# LatchDelay.net
KiCad netlist of a schematic drawn in Altium Designer
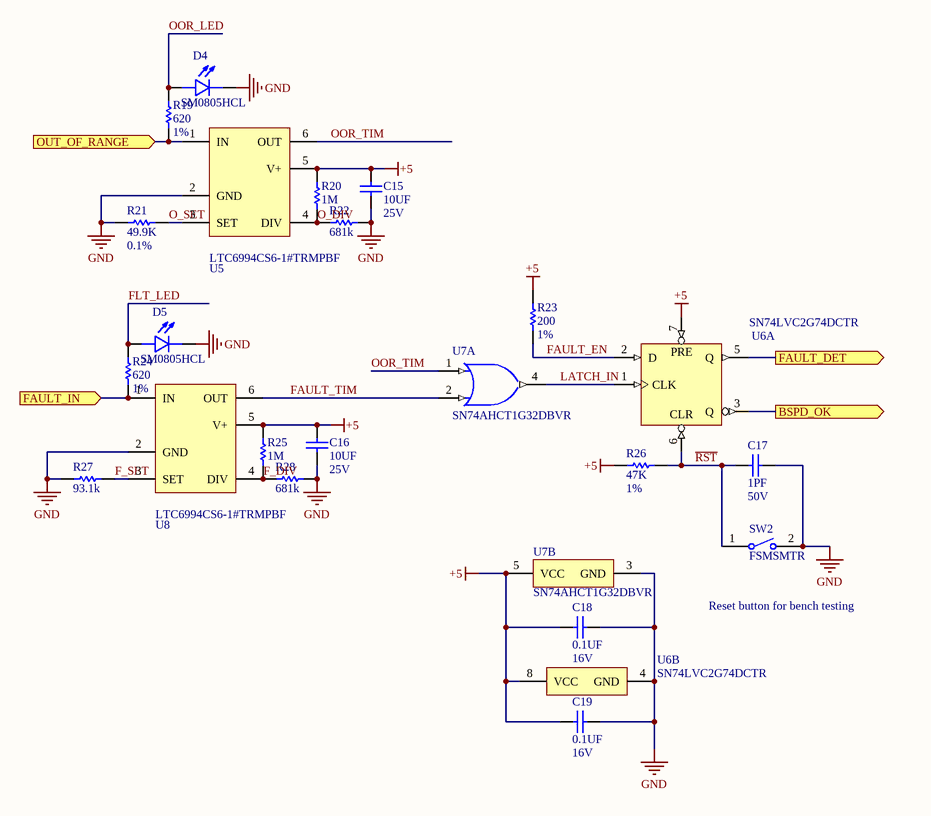
[diagram p0: LatchDelay.SchDoc]

(export (version "E")
  (design (tool "Eeschema 10.0.6"))
  (components
    (comp (ref "C15")
      (value "CAP 0603 10UF 25V 20% X5R")
      (footprint "0603_CAP")
      (description "Capacitor Surface Mount 0603 Footprint 10UF 25V 20% Tolerance Ceramic X5R")
      (fields
        (field (name "VAL") "10UF")
        (field (name "VOL") "25V")
        (field (name "MANUFACTURER") "Various")
        (field (name "VOLTAGE") "25V")
      )
      (libsource (lib "Passive Components") (part "cap"))
    )
    (comp (ref "C16")
      (value "CAP 0603 10UF 25V 20% X5R")
      (footprint "0603_CAP")
      (description "Capacitor Surface Mount 0603 Footprint 10UF 25V 20% Tolerance Ceramic X5R")
      (fields
        (field (name "VAL") "10UF")
        (field (name "VOL") "25V")
        (field (name "MANUFACTURER") "Various")
        (field (name "VOLTAGE") "25V")
      )
      (libsource (lib "Passive Components") (part "cap"))
    )
    (comp (ref "C17")
      (value "CAP 0603 1PF 50V 0.05PF MLO")
      (footprint "0603_CAP")
      (description "Capacitor Surface Mount 0603 Footprint 1PF 50V 0.05PF Tolerance MLO")
      (fields
        (field (name "VAL") "1PF")
        (field (name "VOL") "50V")
        (field (name "MANUFACTURER") "Various")
        (field (name "VOLTAGE") "50V")
      )
      (libsource (lib "Passive Components") (part "cap"))
    )
    (comp (ref "C18")
      (value "CAP 0603 0.1UF 16V 10% X7R")
      (footprint "0603_CAP")
      (description "Capacitor Surface Mount 0603 Footprint 0.1UF 16V 10% Tolerance Ceramic X7R")
      (fields
        (field (name "VAL") "0.1UF")
        (field (name "VOL") "16V")
        (field (name "MANUFACTURER") "Various")
        (field (name "VOLTAGE") "16V")
      )
      (libsource (lib "Passive Components") (part "cap"))
    )
    (comp (ref "C19")
      (value "CAP 0603 0.1UF 16V 10% X7R")
      (footprint "0603_CAP")
      (description "Capacitor Surface Mount 0603 Footprint 0.1UF 16V 10% Tolerance Ceramic X7R")
      (fields
        (field (name "VAL") "0.1UF")
        (field (name "VOL") "16V")
        (field (name "MANUFACTURER") "Various")
        (field (name "VOLTAGE") "16V")
      )
      (libsource (lib "Passive Components") (part "cap"))
    )
    (comp (ref "D4")
      (value "SM0805HCL")
      (footprint "LEDC2012X135N_SM0805HCL(Primary)")
      (description "Red 631nm LED Indication - Discrete 1.9V 0805 (2012 Metric)")
      (libsource (lib "bspd parts") (part "SM0805HCL"))
    )
    (comp (ref "D5")
      (value "SM0805HCL")
      (footprint "LEDC2012X135N_SM0805HCL(Primary)")
      (description "Red 631nm LED Indication - Discrete 1.9V 0805 (2012 Metric)")
      (libsource (lib "bspd parts") (part "SM0805HCL"))
    )
    (comp (ref "R19")
      (value "RES 0603 620 1%")
      (footprint "0603_RES")
      (description "Resistor Surface Mount, 620 Ohms, 0603 Footprint, 1% Tolerance 0.1W")
      (fields
        (field (name "VAL") "620")
        (field (name "TOL") "1%")
        (field (name "MANUFACTURER") "Various")
        (field (name "TOLERANCE") "1%")
      )
      (libsource (lib "Passive Components") (part "res"))
    )
    (comp (ref "R20")
      (value "1M")
      (footprint "RESC2013X60X35ML10T20")
      (fields (field (name "MANUFACTURER") "Yageo") (field (name "PART NUMBER") "RT0805BRE071ML"))
      (libsource (lib "Altium Content Vault") (part "RES"))
    )
    (comp (ref "R21")
      (value "RES 0603 49.9K 0.1%")
      (footprint "0603_RES")
      (description "Resistor Surface Mount, 49.9K Ohms, 0603 Footprint, 0.1% Tolerance 0.1W")
      (fields
        (field (name "VAL") "49.9K")
        (field (name "TOL") "0.1%")
        (field (name "MANUFACTURER") "Various")
        (field (name "TOLERANCE") "0.1%")
      )
      (libsource (lib "Passive Components") (part "res"))
    )
    (comp (ref "R22")
      (value "681k")
      (footprint "RESC2013X60X40NL20T25")
      (fields (field (name "MANUFACTURER") "Panasonic") (field (name "PART NUMBER") "ERA6AEB6813V"))
      (libsource (lib "Altium Content Vault") (part "RES"))
    )
    (comp (ref "R23")
      (value "RES 0603 200 1%")
      (footprint "0603_RES")
      (description "Resistor Surface Mount, 200 Ohms, 0603 Footprint, 1% Tolerance 0.1W")
      (fields
        (field (name "VAL") "200")
        (field (name "TOL") "1%")
        (field (name "MANUFACTURER") "Various")
        (field (name "TOLERANCE") "1%")
      )
      (libsource (lib "Passive Components") (part "res"))
    )
    (comp (ref "R24")
      (value "RES 0603 620 1%")
      (footprint "0603_RES")
      (description "Resistor Surface Mount, 620 Ohms, 0603 Footprint, 1% Tolerance 0.1W")
      (fields
        (field (name "VAL") "620")
        (field (name "TOL") "1%")
        (field (name "MANUFACTURER") "Various")
        (field (name "TOLERANCE") "1%")
      )
      (libsource (lib "Passive Components") (part "res"))
    )
    (comp (ref "R25")
      (value "1M")
      (footprint "RESC2013X60X35ML10T20")
      (fields (field (name "MANUFACTURER") "Yageo") (field (name "PART NUMBER") "RT0805BRE071ML"))
      (libsource (lib "Altium Content Vault") (part "RES"))
    )
    (comp (ref "R26")
      (value "RES 0603 47K 1%")
      (footprint "0603_RES")
      (description "Resistor Surface Mount, 47K Ohms, 0603 Footprint, 1% Tolerance 0.1W")
      (fields
        (field (name "VAL") "47K")
        (field (name "TOL") "1%")
        (field (name "MANUFACTURER") "Various")
        (field (name "TOLERANCE") "1%")
      )
      (libsource (lib "Passive Components") (part "res"))
    )
    (comp (ref "R27")
      (value "93.1k")
      (footprint "RESC1608X50X30NL20T20")
      (fields (field (name "PART NUMBER") "RG1608P-9312-B-T5") (field (name "MANUFACTURER") "Susumu"))
      (libsource (lib "Altium Content Vault") (part "RES"))
    )
    (comp (ref "R28")
      (value "681k")
      (footprint "RESC2013X60X40NL20T25")
      (fields (field (name "MANUFACTURER") "Panasonic") (field (name "PART NUMBER") "ERA6AEB6813V"))
      (libsource (lib "Altium Content Vault") (part "RES"))
    )
    (comp (ref "SW2")
      (value "FSMSMTR")
      (footprint "TECO-FSMSMTR_V")
      (description "FSMSM Push Button Switch, 50 mA, -35 to 85 degC, 2-Pin SMD, RoHS, Tape and Reel")
      (fields (field (name "MANUFACTURER") "TE Connectivity"))
      (libsource (lib "Altium Content Vault") (part "SW-SPST-2_C"))
    )
    (comp (ref "U5")
      (value "LTC6994CS6-1#TRMPBF")
      (footprint "Linear_Technologies_LTC6994CS6-1#TRMPBF_0")
      (description "IC DELAY LINE 8TAP PROG TSOT23-6")
      (fields
        (field (name "DIGIKEY PART NUMBER") "LTC6994CS6-1#TRMPBFCT-ND")
        (field (name "MANUFACTURER") "Linear Technologies")
      )
      (libsource (lib "bspd parts") (part "LTC6994CS6-1#TRMPBF"))
    )
    (comp (ref "U6")
      (value "SN74LVC2G74DCTR")
      (footprint "DCT0008A_M")
      (description "Single Positive-Edge-Triggered D-Type Flip-Flop with Clear and Preset, DCT0008A, LARGE T&R")
      (fields
        (field (name "GENERIC PART NUMBER") "SN74LVC2G74")
        (field (name "MANUFACTURER") "Texas Instruments")
      )
      (libsource (lib "Altium Content Vault") (part "TI-SN74XXX1G74_2G74-8"))
    )
    (comp (ref "U7")
      (value "SN74AHCT1G32DBVR")
      (footprint "DBV0005A_M")
      (description "Single 2-Input Positive-OR Gate, DBV0005A, LARGE T&R")
      (fields
        (field (name "GENERIC PART NUMBER") "SN74AHCT1G32")
        (field (name "MANUFACTURER") "Texas Instruments")
      )
      (libsource (lib "Altium Content Vault") (part "TI-SN74XXX1X32-5"))
    )
    (comp (ref "U8")
      (value "LTC6994CS6-1#TRMPBF")
      (footprint "Linear_Technologies_LTC6994CS6-1#TRMPBF_0")
      (description "IC DELAY LINE 8TAP PROG TSOT23-6")
      (fields
        (field (name "DIGIKEY PART NUMBER") "LTC6994CS6-1#TRMPBFCT-ND")
        (field (name "MANUFACTURER") "Linear Technologies")
      )
      (libsource (lib "bspd parts") (part "LTC6994CS6-1#TRMPBF"))
    )
  )
  (nets
    (net (code "1") (name "+5") (class "Default")
      (node (ref "C15") (pin "2") (pinfunction "2_2") (pintype "passive"))
      (node (ref "C16") (pin "2") (pinfunction "2_2") (pintype "passive"))
      (node (ref "C18") (pin "2") (pinfunction "2_2") (pintype "passive"))
      (node (ref "C19") (pin "2") (pinfunction "2_2") (pintype "passive"))
      (node (ref "R20") (pin "2") (pinfunction "2_2") (pintype "passive"))
      (node (ref "R23") (pin "2") (pinfunction "2_2") (pintype "passive"))
      (node (ref "R25") (pin "2") (pinfunction "2_2") (pintype "passive"))
      (node (ref "R26") (pin "1") (pinfunction "1_1") (pintype "passive"))
      (node (ref "U5") (pin "5") (pinfunction "V+_5") (pintype "passive"))
      (node (ref "U6") (pin "7") (pinfunction "~{PRE}_7") (pintype "input"))
      (node (ref "U6") (pin "8") (pinfunction "VCC_8") (pintype "power_in"))
      (node (ref "U7") (pin "5") (pinfunction "VCC_5") (pintype "power_in"))
      (node (ref "U8") (pin "5") (pinfunction "V+_5") (pintype "passive"))
    )
    (net (code "2") (name "/BSPD_OK") (class "Default")
      (node (ref "U6") (pin "3") (pinfunction "Q_3") (pintype "output"))
    )
    (net (code "3") (name "/FAULT_DET") (class "Default")
      (node (ref "U6") (pin "5") (pinfunction "Q_5") (pintype "output"))
    )
    (net (code "4") (name "/FAULT_EN") (class "Default")
      (node (ref "R23") (pin "1") (pinfunction "1_1") (pintype "passive"))
      (node (ref "U6") (pin "2") (pinfunction "D_2") (pintype "input"))
    )
    (net (code "5") (name "/FAULT_IN") (class "Default")
      (node (ref "R24") (pin "1") (pinfunction "1_1") (pintype "passive"))
      (node (ref "U8") (pin "1") (pinfunction "IN_1") (pintype "passive"))
    )
    (net (code "6") (name "/FAULT_TIM") (class "Default")
      (node (ref "U7") (pin "2") (pinfunction "B_2") (pintype "input"))
      (node (ref "U8") (pin "6") (pinfunction "OUT_6") (pintype "passive"))
    )
    (net (code "7") (name "/FLT_LED") (class "Default")
      (node (ref "D5") (pin "A") (pinfunction "A_A") (pintype "passive"))
      (node (ref "R24") (pin "2") (pinfunction "2_2") (pintype "passive"))
    )
    (net (code "8") (name "/F_DIV") (class "Default")
      (node (ref "R25") (pin "1") (pinfunction "1_1") (pintype "passive"))
      (node (ref "R28") (pin "1") (pinfunction "1_1") (pintype "passive"))
      (node (ref "U8") (pin "4") (pinfunction "DIV_4") (pintype "passive"))
    )
    (net (code "9") (name "/F_SET") (class "Default")
      (node (ref "R27") (pin "2") (pinfunction "2_2") (pintype "passive"))
      (node (ref "U8") (pin "3") (pinfunction "SET_3") (pintype "passive"))
    )
    (net (code "10") (name "/LATCH_IN") (class "Default")
      (node (ref "U6") (pin "1") (pinfunction "CLK_1") (pintype "input"))
      (node (ref "U7") (pin "4") (pinfunction "Y_4") (pintype "output"))
    )
    (net (code "11") (name "/OOR_LED") (class "Default")
      (node (ref "D4") (pin "A") (pinfunction "A_A") (pintype "passive"))
      (node (ref "R19") (pin "2") (pinfunction "2_2") (pintype "passive"))
    )
    (net (code "12") (name "/OOR_TIM") (class "Default")
      (node (ref "U5") (pin "6") (pinfunction "OUT_6") (pintype "passive"))
      (node (ref "U7") (pin "1") (pinfunction "A_1") (pintype "input"))
    )
    (net (code "13") (name "/OUT_OF_RANGE") (class "Default")
      (node (ref "R19") (pin "1") (pinfunction "1_1") (pintype "passive"))
      (node (ref "U5") (pin "1") (pinfunction "IN_1") (pintype "passive"))
    )
    (net (code "14") (name "/O_DIV") (class "Default")
      (node (ref "R20") (pin "1") (pinfunction "1_1") (pintype "passive"))
      (node (ref "R22") (pin "1") (pinfunction "1_1") (pintype "passive"))
      (node (ref "U5") (pin "4") (pinfunction "DIV_4") (pintype "passive"))
    )
    (net (code "15") (name "/O_SET") (class "Default")
      (node (ref "R21") (pin "2") (pinfunction "2_2") (pintype "passive"))
      (node (ref "U5") (pin "3") (pinfunction "SET_3") (pintype "passive"))
    )
    (net (code "16") (name "/RST") (class "Default")
      (node (ref "C17") (pin "1") (pinfunction "1_1") (pintype "passive"))
      (node (ref "R26") (pin "2") (pinfunction "2_2") (pintype "passive"))
      (node (ref "SW2") (pin "1") (pinfunction "1_1") (pintype "passive"))
      (node (ref "U6") (pin "6") (pinfunction "~{CLR}_6") (pintype "input"))
    )
    (net (code "17") (name "GND") (class "Default")
      (node (ref "C15") (pin "1") (pinfunction "1_1") (pintype "passive"))
      (node (ref "C16") (pin "1") (pinfunction "1_1") (pintype "passive"))
      (node (ref "C17") (pin "2") (pinfunction "2_2") (pintype "passive"))
      (node (ref "C18") (pin "1") (pinfunction "1_1") (pintype "passive"))
      (node (ref "C19") (pin "1") (pinfunction "1_1") (pintype "passive"))
      (node (ref "D4") (pin "C") (pinfunction "C_C") (pintype "passive"))
      (node (ref "D5") (pin "C") (pinfunction "C_C") (pintype "passive"))
      (node (ref "R21") (pin "1") (pinfunction "1_1") (pintype "passive"))
      (node (ref "R22") (pin "2") (pinfunction "2_2") (pintype "passive"))
      (node (ref "R27") (pin "1") (pinfunction "1_1") (pintype "passive"))
      (node (ref "R28") (pin "2") (pinfunction "2_2") (pintype "passive"))
      (node (ref "SW2") (pin "2") (pinfunction "2_2") (pintype "passive"))
      (node (ref "U5") (pin "2") (pinfunction "GND_2") (pintype "passive"))
      (node (ref "U6") (pin "4") (pinfunction "GND_4") (pintype "power_in"))
      (node (ref "U7") (pin "3") (pinfunction "GND_3") (pintype "power_in"))
      (node (ref "U8") (pin "2") (pinfunction "GND_2") (pintype "passive"))
    )
  )
)
